# MSlave.net
KiCad netlist of a schematic drawn in EAGLE
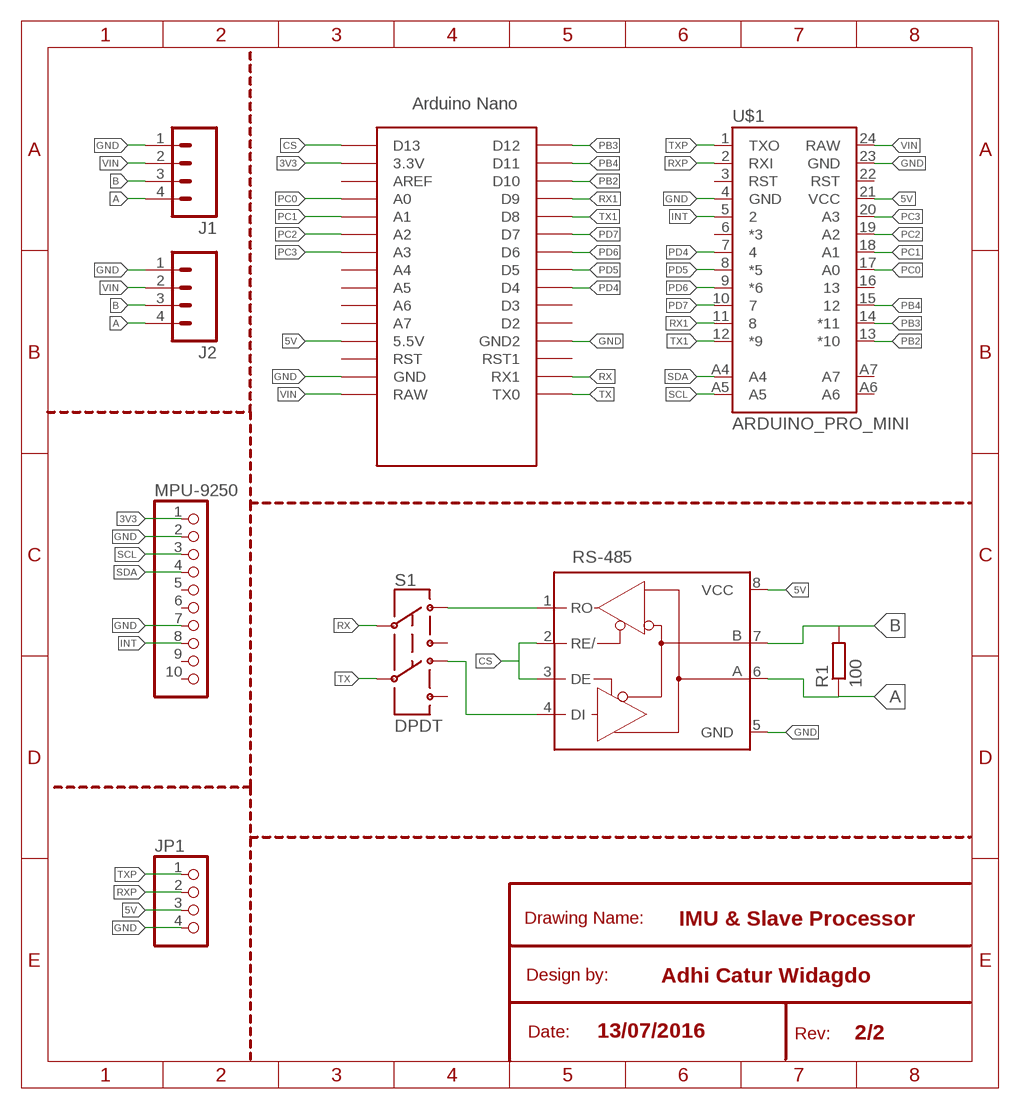
[diagram p0: schematic, sheet 1]

(export (version "E")
  (design (tool "Eeschema 10.0.6"))
  (components
    (comp (ref "J1")
      (value "M04POLAR")
      (footprint "eagle-import:MOLEX-1X4")
      (libsource (lib "eagle-import") (part "M04POLAR"))
    )
    (comp (ref "J2")
      (value "M04POLAR")
      (footprint "eagle-import:MOLEX-1X4")
      (libsource (lib "eagle-import") (part "M04POLAR"))
    )
    (comp (ref "JP1")
      (value "PINHD-1X4")
      (footprint "eagle-import:1X04")
      (libsource (lib "eagle-import") (part "PINHD-1X4"))
    )
    (comp (ref "MCU_SLAVE")
      (value "MCU_Slave")
      (footprint "eagle-import:NANO")
      (libsource (lib "eagle-import") (part "NANO"))
    )
    (comp (ref "MPU-9250")
      (value "PINHD-1X10")
      (footprint "eagle-import:1X10")
      (libsource (lib "eagle-import") (part "PINHD-1X10"))
    )
    (comp (ref "R1")
      (value "100")
      (footprint "eagle-import:0204_7")
      (libsource (lib "eagle-import") (part "R-EU_0204/7"))
    )
    (comp (ref "RS-485")
      (value "MAX3468CPA")
      (footprint "eagle-import:DIL08")
      (libsource (lib "eagle-import") (part "MAX34PA68C"))
    )
    (comp (ref "S1")
      (value "DPDT")
      (footprint "eagle-import:AYZ0202")
      (libsource (lib "eagle-import") (part "SWITCH-DPDTAYZ0202"))
    )
    (comp (ref "U$1")
      (value "ARDUINO_PRO_MINI")
      (footprint "eagle-import:ARDUINO_PRO_MINI")
      (libsource (lib "eagle-import") (part "ARDUINO_PRO_MINI"))
    )
  )
  (nets
    (net (code "1") (name "3V3") (class "Default")
      (node (ref "MCU_SLAVE") (pin "3.3V") (pinfunction "3.3V_3.3V") (pintype "bidirectional"))
      (node (ref "MPU-9250") (pin "1") (pinfunction "1_1") (pintype "passive"))
    )
    (net (code "2") (name "5V") (class "Default")
      (node (ref "JP1") (pin "3") (pinfunction "3_3") (pintype "passive"))
      (node (ref "MCU_SLAVE") (pin "5V") (pinfunction "5.5V_5V") (pintype "bidirectional"))
      (node (ref "RS-485") (pin "8") (pinfunction "VCC_8") (pintype "power_in"))
      (node (ref "U$1") (pin "21") (pinfunction "VCC_21") (pintype "bidirectional"))
    )
    (net (code "3") (name "A") (class "Default")
      (node (ref "J1") (pin "4") (pinfunction "4_4") (pintype "passive"))
      (node (ref "J2") (pin "4") (pinfunction "4_4") (pintype "passive"))
      (node (ref "R1") (pin "1") (pinfunction "1_1") (pintype "passive"))
      (node (ref "RS-485") (pin "6") (pinfunction "A_6") (pintype "passive"))
    )
    (net (code "4") (name "B") (class "Default")
      (node (ref "J1") (pin "3") (pinfunction "3_3") (pintype "passive"))
      (node (ref "J2") (pin "3") (pinfunction "3_3") (pintype "passive"))
      (node (ref "R1") (pin "2") (pinfunction "2_2") (pintype "passive"))
      (node (ref "RS-485") (pin "7") (pinfunction "B_7") (pintype "passive"))
    )
    (net (code "5") (name "CS") (class "Default")
      (node (ref "MCU_SLAVE") (pin "D13") (pinfunction "D13_D13") (pintype "bidirectional"))
      (node (ref "RS-485") (pin "2") (pinfunction "RE/_2") (pintype "input"))
      (node (ref "RS-485") (pin "3") (pinfunction "DE_3") (pintype "input"))
    )
    (net (code "6") (name "GND") (class "Default")
      (node (ref "J1") (pin "1") (pinfunction "1_1") (pintype "passive"))
      (node (ref "J2") (pin "1") (pinfunction "1_1") (pintype "passive"))
      (node (ref "JP1") (pin "4") (pinfunction "4_4") (pintype "passive"))
      (node (ref "MCU_SLAVE") (pin "GND") (pinfunction "GND_GND") (pintype "bidirectional"))
      (node (ref "MCU_SLAVE") (pin "GND1") (pinfunction "GND2_GND1") (pintype "bidirectional"))
      (node (ref "MPU-9250") (pin "2") (pinfunction "2_2") (pintype "passive"))
      (node (ref "MPU-9250") (pin "7") (pinfunction "7_7") (pintype "passive"))
      (node (ref "RS-485") (pin "5") (pinfunction "GND_5") (pintype "power_in"))
      (node (ref "U$1") (pin "23") (pinfunction "GND_23") (pintype "bidirectional"))
      (node (ref "U$1") (pin "4") (pinfunction "GND_4") (pintype "bidirectional"))
    )
    (net (code "7") (name "INT") (class "Default")
      (node (ref "MPU-9250") (pin "8") (pinfunction "8_8") (pintype "passive"))
      (node (ref "U$1") (pin "5") (pinfunction "2_5") (pintype "bidirectional"))
    )
    (net (code "8") (name "Net-(RS-485-DI)") (class "Default")
      (node (ref "RS-485") (pin "4") (pinfunction "DI_4") (pintype "input"))
      (node (ref "S1") (pin "4") (pinfunction "4_4") (pintype "bidirectional"))
    )
    (net (code "9") (name "Net-(RS-485-RO)") (class "Default")
      (node (ref "RS-485") (pin "1") (pinfunction "RO_1") (pintype "output"))
      (node (ref "S1") (pin "1") (pinfunction "1_1") (pintype "bidirectional"))
    )
    (net (code "10") (name "PB2") (class "Default")
      (node (ref "MCU_SLAVE") (pin "D10") (pinfunction "D10_D10") (pintype "bidirectional"))
      (node (ref "U$1") (pin "13") (pinfunction "*10_13") (pintype "bidirectional"))
    )
    (net (code "11") (name "PB3") (class "Default")
      (node (ref "MCU_SLAVE") (pin "D12") (pinfunction "D12_D12") (pintype "bidirectional"))
      (node (ref "U$1") (pin "14") (pinfunction "*11_14") (pintype "bidirectional"))
    )
    (net (code "12") (name "PB4") (class "Default")
      (node (ref "MCU_SLAVE") (pin "D11") (pinfunction "D11_D11") (pintype "bidirectional"))
      (node (ref "U$1") (pin "15") (pinfunction "12_15") (pintype "bidirectional"))
    )
    (net (code "13") (name "PC0") (class "Default")
      (node (ref "MCU_SLAVE") (pin "A0") (pinfunction "A0_A0") (pintype "bidirectional"))
      (node (ref "U$1") (pin "17") (pinfunction "A0_17") (pintype "bidirectional"))
    )
    (net (code "14") (name "PC1") (class "Default")
      (node (ref "MCU_SLAVE") (pin "A1") (pinfunction "A1_A1") (pintype "bidirectional"))
      (node (ref "U$1") (pin "18") (pinfunction "A1_18") (pintype "bidirectional"))
    )
    (net (code "15") (name "PC2") (class "Default")
      (node (ref "MCU_SLAVE") (pin "A2") (pinfunction "A2_A2") (pintype "bidirectional"))
      (node (ref "U$1") (pin "19") (pinfunction "A2_19") (pintype "bidirectional"))
    )
    (net (code "16") (name "PC3") (class "Default")
      (node (ref "MCU_SLAVE") (pin "A3") (pinfunction "A3_A3") (pintype "bidirectional"))
      (node (ref "U$1") (pin "20") (pinfunction "A3_20") (pintype "bidirectional"))
    )
    (net (code "17") (name "PD4") (class "Default")
      (node (ref "MCU_SLAVE") (pin "D4") (pinfunction "D4_D4") (pintype "bidirectional"))
      (node (ref "U$1") (pin "7") (pinfunction "4_7") (pintype "bidirectional"))
    )
    (net (code "18") (name "PD5") (class "Default")
      (node (ref "MCU_SLAVE") (pin "D5") (pinfunction "D5_D5") (pintype "bidirectional"))
      (node (ref "U$1") (pin "8") (pinfunction "*5_8") (pintype "bidirectional"))
    )
    (net (code "19") (name "PD6") (class "Default")
      (node (ref "MCU_SLAVE") (pin "D6") (pinfunction "D6_D6") (pintype "bidirectional"))
      (node (ref "U$1") (pin "9") (pinfunction "*6_9") (pintype "bidirectional"))
    )
    (net (code "20") (name "PD7") (class "Default")
      (node (ref "MCU_SLAVE") (pin "D7") (pinfunction "D7_D7") (pintype "bidirectional"))
      (node (ref "U$1") (pin "10") (pinfunction "7_10") (pintype "bidirectional"))
    )
    (net (code "21") (name "RX") (class "Default")
      (node (ref "MCU_SLAVE") (pin "RX1") (pinfunction "RX1_RX1") (pintype "bidirectional"))
      (node (ref "S1") (pin "2") (pinfunction "2_2") (pintype "bidirectional"))
    )
    (net (code "22") (name "RX1") (class "Default")
      (node (ref "MCU_SLAVE") (pin "D9") (pinfunction "D9_D9") (pintype "bidirectional"))
      (node (ref "U$1") (pin "11") (pinfunction "8_11") (pintype "bidirectional"))
    )
    (net (code "23") (name "RXP") (class "Default")
      (node (ref "JP1") (pin "2") (pinfunction "2_2") (pintype "passive"))
      (node (ref "U$1") (pin "2") (pinfunction "RXI_2") (pintype "bidirectional"))
    )
    (net (code "24") (name "SCL") (class "Default")
      (node (ref "MPU-9250") (pin "3") (pinfunction "3_3") (pintype "passive"))
      (node (ref "U$1") (pin "A5") (pinfunction "A5_A5") (pintype "bidirectional"))
    )
    (net (code "25") (name "SDA") (class "Default")
      (node (ref "MPU-9250") (pin "4") (pinfunction "4_4") (pintype "passive"))
      (node (ref "U$1") (pin "A4") (pinfunction "A4_A4") (pintype "bidirectional"))
    )
    (net (code "26") (name "TX") (class "Default")
      (node (ref "MCU_SLAVE") (pin "TX0") (pinfunction "TX0_TX0") (pintype "bidirectional"))
      (node (ref "S1") (pin "5") (pinfunction "5_5") (pintype "bidirectional"))
    )
    (net (code "27") (name "TX1") (class "Default")
      (node (ref "MCU_SLAVE") (pin "D8") (pinfunction "D8_D8") (pintype "bidirectional"))
      (node (ref "U$1") (pin "12") (pinfunction "*9_12") (pintype "bidirectional"))
    )
    (net (code "28") (name "TXP") (class "Default")
      (node (ref "JP1") (pin "1") (pinfunction "1_1") (pintype "passive"))
      (node (ref "U$1") (pin "1") (pinfunction "TXO_1") (pintype "bidirectional"))
    )
    (net (code "29") (name "VIN") (class "Default")
      (node (ref "J1") (pin "2") (pinfunction "2_2") (pintype "passive"))
      (node (ref "J2") (pin "2") (pinfunction "2_2") (pintype "passive"))
      (node (ref "MCU_SLAVE") (pin "RAW") (pinfunction "RAW_RAW") (pintype "bidirectional"))
      (node (ref "U$1") (pin "24") (pinfunction "RAW_24") (pintype "bidirectional"))
    )
    (net (code "30") (name "unconnected-(MCU_SLAVE-PadA4)") (class "Default")
      (node (ref "MCU_SLAVE") (pin "A4") (pinfunction "A4_A4") (pintype "bidirectional"))
    )
    (net (code "31") (name "unconnected-(MCU_SLAVE-PadA5)") (class "Default")
      (node (ref "MCU_SLAVE") (pin "A5") (pinfunction "A5_A5") (pintype "bidirectional"))
    )
    (net (code "32") (name "unconnected-(MCU_SLAVE-PadA6)") (class "Default")
      (node (ref "MCU_SLAVE") (pin "A6") (pinfunction "A6_A6") (pintype "bidirectional"))
    )
    (net (code "33") (name "unconnected-(MCU_SLAVE-PadA7)") (class "Default")
      (node (ref "MCU_SLAVE") (pin "A7") (pinfunction "A7_A7") (pintype "bidirectional"))
    )
    (net (code "34") (name "unconnected-(MCU_SLAVE-PadAREF)") (class "Default")
      (node (ref "MCU_SLAVE") (pin "AREF") (pinfunction "AREF_AREF") (pintype "bidirectional"))
    )
    (net (code "35") (name "unconnected-(MCU_SLAVE-PadD2)") (class "Default")
      (node (ref "MCU_SLAVE") (pin "D2") (pinfunction "D2_D2") (pintype "bidirectional"))
    )
    (net (code "36") (name "unconnected-(MCU_SLAVE-PadD3)") (class "Default")
      (node (ref "MCU_SLAVE") (pin "D3") (pinfunction "D3_D3") (pintype "bidirectional"))
    )
    (net (code "37") (name "unconnected-(MCU_SLAVE-PadICSP1)") (class "Default")
      (node (ref "MCU_SLAVE") (pin "ICSP1") (pinfunction "ICSP1_ICSP1") (pintype "bidirectional"))
    )
    (net (code "38") (name "unconnected-(MCU_SLAVE-PadICSP2)") (class "Default")
      (node (ref "MCU_SLAVE") (pin "ICSP2") (pinfunction "ICSP2_ICSP2") (pintype "bidirectional"))
    )
    (net (code "39") (name "unconnected-(MCU_SLAVE-PadICSP3)") (class "Default")
      (node (ref "MCU_SLAVE") (pin "ICSP3") (pinfunction "ICSP3_ICSP3") (pintype "bidirectional"))
    )
    (net (code "40") (name "unconnected-(MCU_SLAVE-PadICSP4)") (class "Default")
      (node (ref "MCU_SLAVE") (pin "ICSP4") (pinfunction "ICSP4_ICSP4") (pintype "bidirectional"))
    )
    (net (code "41") (name "unconnected-(MCU_SLAVE-PadICSP5)") (class "Default")
      (node (ref "MCU_SLAVE") (pin "ICSP5") (pinfunction "ICSP5_ICSP5") (pintype "bidirectional"))
    )
    (net (code "42") (name "unconnected-(MCU_SLAVE-PadICSP6)") (class "Default")
      (node (ref "MCU_SLAVE") (pin "ICSP6") (pinfunction "ICSP6_ICSP6") (pintype "bidirectional"))
    )
    (net (code "43") (name "unconnected-(MCU_SLAVE-PadRST)") (class "Default")
      (node (ref "MCU_SLAVE") (pin "RST") (pinfunction "RST_RST") (pintype "bidirectional"))
    )
    (net (code "44") (name "unconnected-(MCU_SLAVE-PadRST1)") (class "Default")
      (node (ref "MCU_SLAVE") (pin "RST1") (pinfunction "RST1_RST1") (pintype "bidirectional"))
    )
    (net (code "45") (name "unconnected-(MPU-9250-Pad5)") (class "Default")
      (node (ref "MPU-9250") (pin "5") (pinfunction "5_5") (pintype "passive"))
    )
    (net (code "46") (name "unconnected-(MPU-9250-Pad6)") (class "Default")
      (node (ref "MPU-9250") (pin "6") (pinfunction "6_6") (pintype "passive"))
    )
    (net (code "47") (name "unconnected-(MPU-9250-Pad9)") (class "Default")
      (node (ref "MPU-9250") (pin "9") (pinfunction "9_9") (pintype "passive"))
    )
    (net (code "48") (name "unconnected-(MPU-9250-Pad10)") (class "Default")
      (node (ref "MPU-9250") (pin "10") (pinfunction "10_10") (pintype "passive"))
    )
    (net (code "49") (name "unconnected-(S1-Pad3)") (class "Default")
      (node (ref "S1") (pin "3") (pinfunction "3_3") (pintype "bidirectional"))
    )
    (net (code "50") (name "unconnected-(S1-Pad6)") (class "Default")
      (node (ref "S1") (pin "6") (pinfunction "6_6") (pintype "bidirectional"))
    )
    (net (code "51") (name "unconnected-(U$1-*3-Pad6)") (class "Default")
      (node (ref "U$1") (pin "6") (pinfunction "*3_6") (pintype "bidirectional"))
    )
    (net (code "52") (name "unconnected-(U$1-13-Pad16)") (class "Default")
      (node (ref "U$1") (pin "16") (pinfunction "13_16") (pintype "bidirectional"))
    )
    (net (code "53") (name "unconnected-(U$1-PadA6)") (class "Default")
      (node (ref "U$1") (pin "A6") (pinfunction "A6_A6") (pintype "bidirectional"))
    )
    (net (code "54") (name "unconnected-(U$1-PadA7)") (class "Default")
      (node (ref "U$1") (pin "A7") (pinfunction "A7_A7") (pintype "bidirectional"))
    )
    (net (code "55") (name "unconnected-(U$1-RST-Pad3)") (class "Default")
      (node (ref "U$1") (pin "3") (pinfunction "RST_3") (pintype "bidirectional"))
    )
    (net (code "56") (name "unconnected-(U$1-RST-Pad22)") (class "Default")
      (node (ref "U$1") (pin "22") (pinfunction "RST_22") (pintype "bidirectional"))
    )
  )
)
